# MCPGrundplatte16UniversalInputoutput.net
KiCad netlist of a schematic drawn in EAGLE
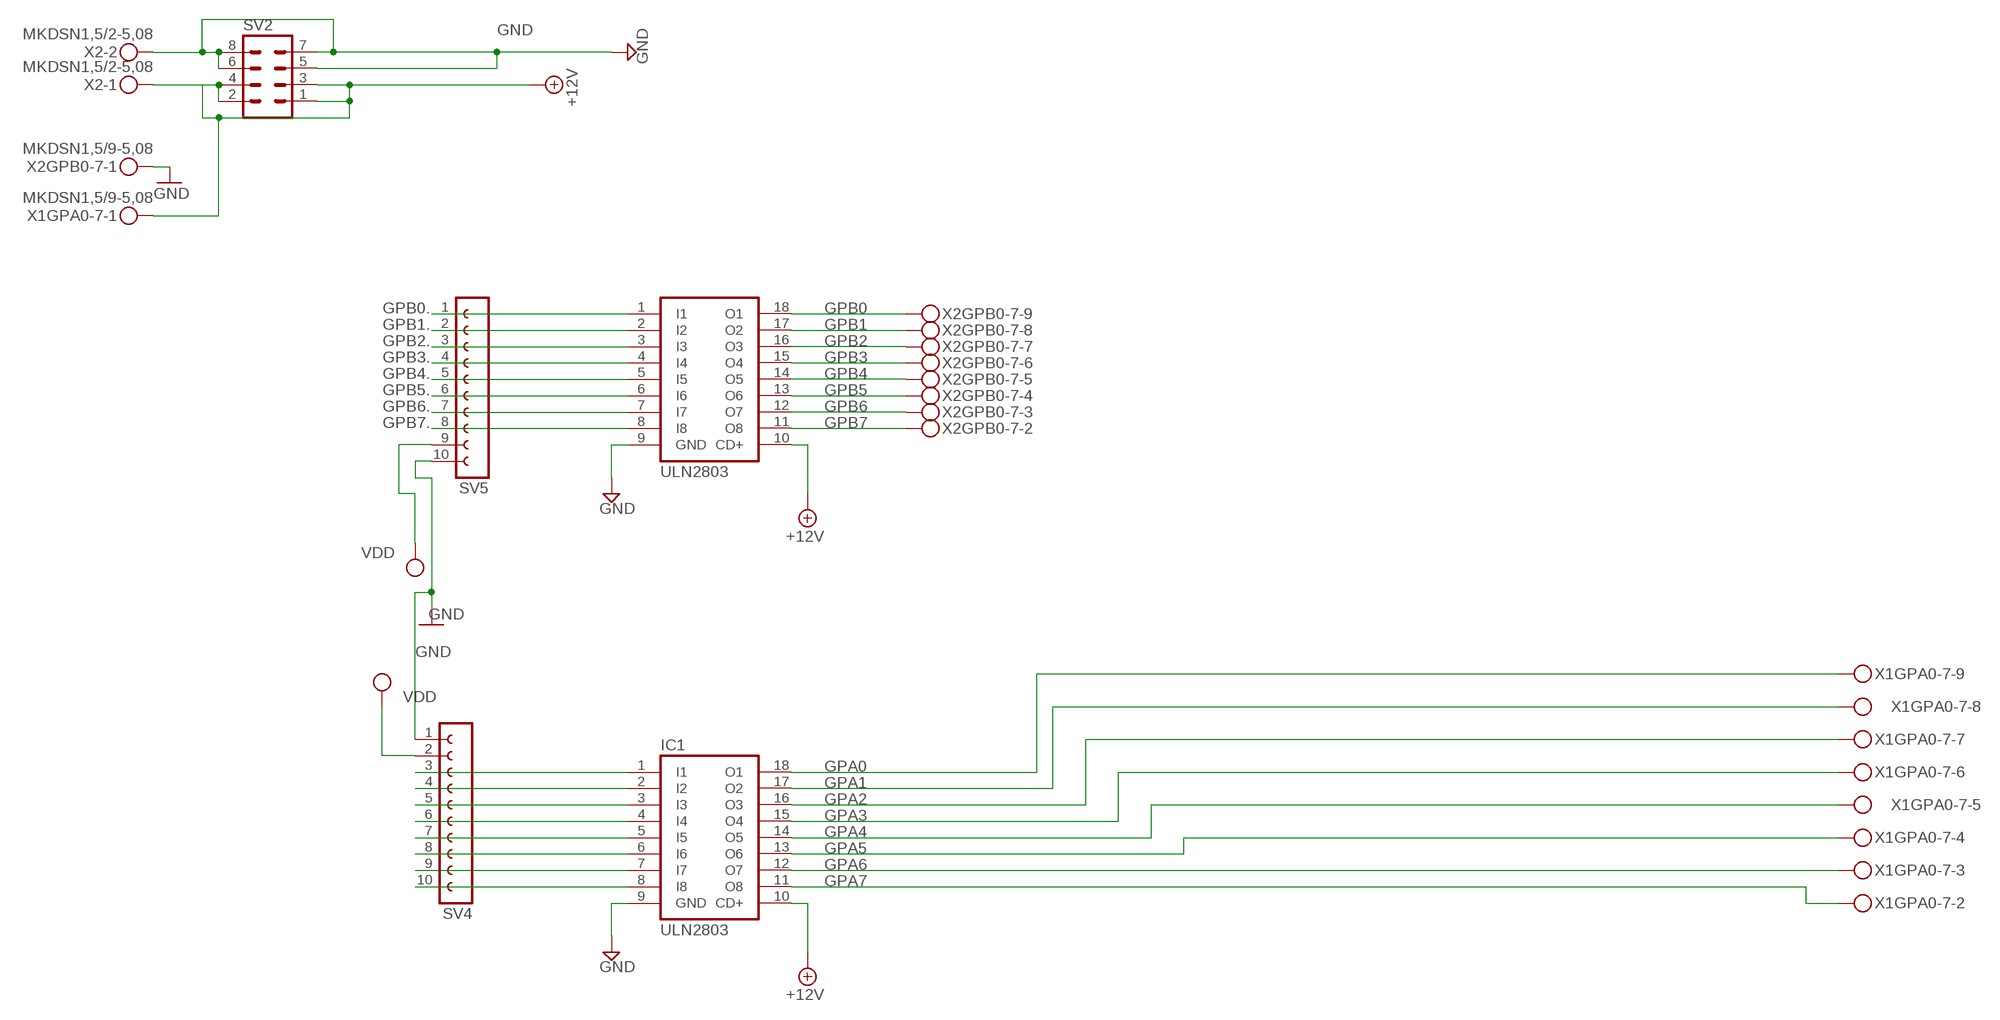
[diagram p0: schematic, sheet 1]

(export (version "E")
  (design (tool "Eeschema 10.0.6"))
  (components
    (comp (ref "IC1")
      (value "ULN2803")
      (footprint "eagle-import:DIL18")
      (libsource (lib "eagle-import") (part "ULN2803A"))
    )
    (comp (ref "IC4")
      (value "ULN2803")
      (footprint "eagle-import:DIL18")
      (libsource (lib "eagle-import") (part "ULN2803A"))
    )
    (comp (ref "SV2")
      (value "MA04-2")
      (footprint "eagle-import:MA04-2")
      (libsource (lib "eagle-import") (part "MA04-2"))
    )
    (comp (ref "SV4")
      (value "FE10-1")
      (footprint "eagle-import:FE10")
      (libsource (lib "eagle-import") (part "FE10-1"))
    )
    (comp (ref "SV5")
      (value "FE10-1")
      (footprint "eagle-import:FE10")
      (libsource (lib "eagle-import") (part "FE10-1"))
    )
    (comp (ref "X1GPA0-7")
      (value "MKDSN1,5/9-5,08")
      (footprint "eagle-import:MKDSN1,5_9-5,08")
      (libsource (lib "eagle-import") (part "MKDSN1,5/9-5,08"))
    )
    (comp (ref "X2")
      (value "MKDSN1,5/2-5,08")
      (footprint "eagle-import:MKDSN1,5_2-5,08")
      (libsource (lib "eagle-import") (part "MKDSN1,5/2-5,08"))
    )
    (comp (ref "X2GPB0-7")
      (value "MKDSN1,5/9-5,08")
      (footprint "eagle-import:MKDSN1,5_9-5,08")
      (libsource (lib "eagle-import") (part "MKDSN1,5/9-5,08"))
    )
  )
  (nets
    (net (code "1") (name "+12V") (class "Default")
      (node (ref "IC1") (pin "10") (pinfunction "CD+_10") (pintype "passive"))
      (node (ref "IC4") (pin "10") (pinfunction "CD+_10") (pintype "passive"))
      (node (ref "SV2") (pin "1") (pinfunction "1_1") (pintype "passive"))
      (node (ref "SV2") (pin "2") (pinfunction "2_2") (pintype "passive"))
      (node (ref "SV2") (pin "3") (pinfunction "3_3") (pintype "passive"))
      (node (ref "SV2") (pin "4") (pinfunction "4_4") (pintype "passive"))
      (node (ref "X1GPA0-7") (pin "1") (pinfunction "KL_1") (pintype "passive"))
      (node (ref "X2") (pin "1") (pinfunction "KL_1") (pintype "passive"))
    )
    (net (code "2") (name "/GPA0") (class "Default")
      (node (ref "IC1") (pin "18") (pinfunction "O1_18") (pintype "open_collector"))
      (node (ref "X1GPA0-7") (pin "9") (pinfunction "KL_9") (pintype "passive"))
    )
    (net (code "3") (name "/GPA1") (class "Default")
      (node (ref "IC1") (pin "17") (pinfunction "O2_17") (pintype "open_collector"))
      (node (ref "X1GPA0-7") (pin "8") (pinfunction "KL_8") (pintype "passive"))
    )
    (net (code "4") (name "/GPA2") (class "Default")
      (node (ref "IC1") (pin "16") (pinfunction "O3_16") (pintype "open_collector"))
      (node (ref "X1GPA0-7") (pin "7") (pinfunction "KL_7") (pintype "passive"))
    )
    (net (code "5") (name "/GPA3") (class "Default")
      (node (ref "IC1") (pin "15") (pinfunction "O4_15") (pintype "open_collector"))
      (node (ref "X1GPA0-7") (pin "6") (pinfunction "KL_6") (pintype "passive"))
    )
    (net (code "6") (name "/GPA4") (class "Default")
      (node (ref "IC1") (pin "14") (pinfunction "O5_14") (pintype "open_collector"))
      (node (ref "X1GPA0-7") (pin "5") (pinfunction "KL_5") (pintype "passive"))
    )
    (net (code "7") (name "/GPA5") (class "Default")
      (node (ref "IC1") (pin "13") (pinfunction "O6_13") (pintype "open_collector"))
      (node (ref "X1GPA0-7") (pin "4") (pinfunction "KL_4") (pintype "passive"))
    )
    (net (code "8") (name "/GPA6") (class "Default")
      (node (ref "IC1") (pin "12") (pinfunction "O7_12") (pintype "open_collector"))
      (node (ref "X1GPA0-7") (pin "3") (pinfunction "KL_3") (pintype "passive"))
    )
    (net (code "9") (name "/GPA7") (class "Default")
      (node (ref "IC1") (pin "11") (pinfunction "O8_11") (pintype "open_collector"))
      (node (ref "X1GPA0-7") (pin "2") (pinfunction "KL_2") (pintype "passive"))
    )
    (net (code "10") (name "/GPB0") (class "Default")
      (node (ref "IC4") (pin "18") (pinfunction "O1_18") (pintype "open_collector"))
      (node (ref "X2GPB0-7") (pin "9") (pinfunction "KL_9") (pintype "passive"))
    )
    (net (code "11") (name "/GPB0.") (class "Default")
      (node (ref "IC4") (pin "1") (pinfunction "I1_1") (pintype "input"))
      (node (ref "SV5") (pin "1") (pinfunction "1_1") (pintype "passive"))
    )
    (net (code "12") (name "/GPB1") (class "Default")
      (node (ref "IC4") (pin "17") (pinfunction "O2_17") (pintype "open_collector"))
      (node (ref "X2GPB0-7") (pin "8") (pinfunction "KL_8") (pintype "passive"))
    )
    (net (code "13") (name "/GPB1.") (class "Default")
      (node (ref "IC4") (pin "2") (pinfunction "I2_2") (pintype "input"))
      (node (ref "SV5") (pin "2") (pinfunction "2_2") (pintype "passive"))
    )
    (net (code "14") (name "/GPB2") (class "Default")
      (node (ref "IC4") (pin "16") (pinfunction "O3_16") (pintype "open_collector"))
      (node (ref "X2GPB0-7") (pin "7") (pinfunction "KL_7") (pintype "passive"))
    )
    (net (code "15") (name "/GPB2.") (class "Default")
      (node (ref "IC4") (pin "3") (pinfunction "I3_3") (pintype "input"))
      (node (ref "SV5") (pin "3") (pinfunction "3_3") (pintype "passive"))
    )
    (net (code "16") (name "/GPB3") (class "Default")
      (node (ref "IC4") (pin "15") (pinfunction "O4_15") (pintype "open_collector"))
      (node (ref "X2GPB0-7") (pin "6") (pinfunction "KL_6") (pintype "passive"))
    )
    (net (code "17") (name "/GPB3.") (class "Default")
      (node (ref "IC4") (pin "4") (pinfunction "I4_4") (pintype "input"))
      (node (ref "SV5") (pin "4") (pinfunction "4_4") (pintype "passive"))
    )
    (net (code "18") (name "/GPB4") (class "Default")
      (node (ref "IC4") (pin "14") (pinfunction "O5_14") (pintype "open_collector"))
      (node (ref "X2GPB0-7") (pin "5") (pinfunction "KL_5") (pintype "passive"))
    )
    (net (code "19") (name "/GPB4.") (class "Default")
      (node (ref "IC4") (pin "5") (pinfunction "I5_5") (pintype "input"))
      (node (ref "SV5") (pin "5") (pinfunction "5_5") (pintype "passive"))
    )
    (net (code "20") (name "/GPB5") (class "Default")
      (node (ref "IC4") (pin "13") (pinfunction "O6_13") (pintype "open_collector"))
      (node (ref "X2GPB0-7") (pin "4") (pinfunction "KL_4") (pintype "passive"))
    )
    (net (code "21") (name "/GPB5.") (class "Default")
      (node (ref "IC4") (pin "6") (pinfunction "I6_6") (pintype "input"))
      (node (ref "SV5") (pin "6") (pinfunction "6_6") (pintype "passive"))
    )
    (net (code "22") (name "/GPB6") (class "Default")
      (node (ref "IC4") (pin "12") (pinfunction "O7_12") (pintype "open_collector"))
      (node (ref "X2GPB0-7") (pin "3") (pinfunction "KL_3") (pintype "passive"))
    )
    (net (code "23") (name "/GPB6.") (class "Default")
      (node (ref "IC4") (pin "7") (pinfunction "I7_7") (pintype "input"))
      (node (ref "SV5") (pin "7") (pinfunction "7_7") (pintype "passive"))
    )
    (net (code "24") (name "/GPB7") (class "Default")
      (node (ref "IC4") (pin "11") (pinfunction "O8_11") (pintype "open_collector"))
      (node (ref "X2GPB0-7") (pin "2") (pinfunction "KL_2") (pintype "passive"))
    )
    (net (code "25") (name "/GPB7.") (class "Default")
      (node (ref "IC4") (pin "8") (pinfunction "I8_8") (pintype "input"))
      (node (ref "SV5") (pin "8") (pinfunction "8_8") (pintype "passive"))
    )
    (net (code "26") (name "GND") (class "Default")
      (node (ref "IC1") (pin "9") (pinfunction "GND_9") (pintype "power_in"))
      (node (ref "IC4") (pin "9") (pinfunction "GND_9") (pintype "power_in"))
      (node (ref "SV2") (pin "5") (pinfunction "5_5") (pintype "passive"))
      (node (ref "SV2") (pin "6") (pinfunction "6_6") (pintype "passive"))
      (node (ref "SV2") (pin "7") (pinfunction "7_7") (pintype "passive"))
      (node (ref "SV2") (pin "8") (pinfunction "8_8") (pintype "passive"))
      (node (ref "SV4") (pin "1") (pinfunction "1_1") (pintype "passive"))
      (node (ref "SV5") (pin "10") (pinfunction "10_10") (pintype "passive"))
      (node (ref "X2") (pin "2") (pinfunction "KL_2") (pintype "passive"))
      (node (ref "X2GPB0-7") (pin "1") (pinfunction "KL_1") (pintype "passive"))
    )
    (net (code "27") (name "Net-(IC1-I1)") (class "Default")
      (node (ref "IC1") (pin "1") (pinfunction "I1_1") (pintype "input"))
      (node (ref "SV4") (pin "3") (pinfunction "3_3") (pintype "passive"))
    )
    (net (code "28") (name "Net-(IC1-I2)") (class "Default")
      (node (ref "IC1") (pin "2") (pinfunction "I2_2") (pintype "input"))
      (node (ref "SV4") (pin "4") (pinfunction "4_4") (pintype "passive"))
    )
    (net (code "29") (name "Net-(IC1-I3)") (class "Default")
      (node (ref "IC1") (pin "3") (pinfunction "I3_3") (pintype "input"))
      (node (ref "SV4") (pin "5") (pinfunction "5_5") (pintype "passive"))
    )
    (net (code "30") (name "Net-(IC1-I4)") (class "Default")
      (node (ref "IC1") (pin "4") (pinfunction "I4_4") (pintype "input"))
      (node (ref "SV4") (pin "6") (pinfunction "6_6") (pintype "passive"))
    )
    (net (code "31") (name "Net-(IC1-I5)") (class "Default")
      (node (ref "IC1") (pin "5") (pinfunction "I5_5") (pintype "input"))
      (node (ref "SV4") (pin "7") (pinfunction "7_7") (pintype "passive"))
    )
    (net (code "32") (name "Net-(IC1-I6)") (class "Default")
      (node (ref "IC1") (pin "6") (pinfunction "I6_6") (pintype "input"))
      (node (ref "SV4") (pin "8") (pinfunction "8_8") (pintype "passive"))
    )
    (net (code "33") (name "Net-(IC1-I7)") (class "Default")
      (node (ref "IC1") (pin "7") (pinfunction "I7_7") (pintype "input"))
      (node (ref "SV4") (pin "9") (pinfunction "9_9") (pintype "passive"))
    )
    (net (code "34") (name "Net-(IC1-I8)") (class "Default")
      (node (ref "IC1") (pin "8") (pinfunction "I8_8") (pintype "input"))
      (node (ref "SV4") (pin "10") (pinfunction "10_10") (pintype "passive"))
    )
    (net (code "35") (name "VDD") (class "Default")
      (node (ref "SV4") (pin "2") (pinfunction "2_2") (pintype "passive"))
      (node (ref "SV5") (pin "9") (pinfunction "9_9") (pintype "passive"))
    )
  )
)
